# Ai_Breakout_OLED-0_96.net
KiCad netlist of a schematic drawn in EAGLE
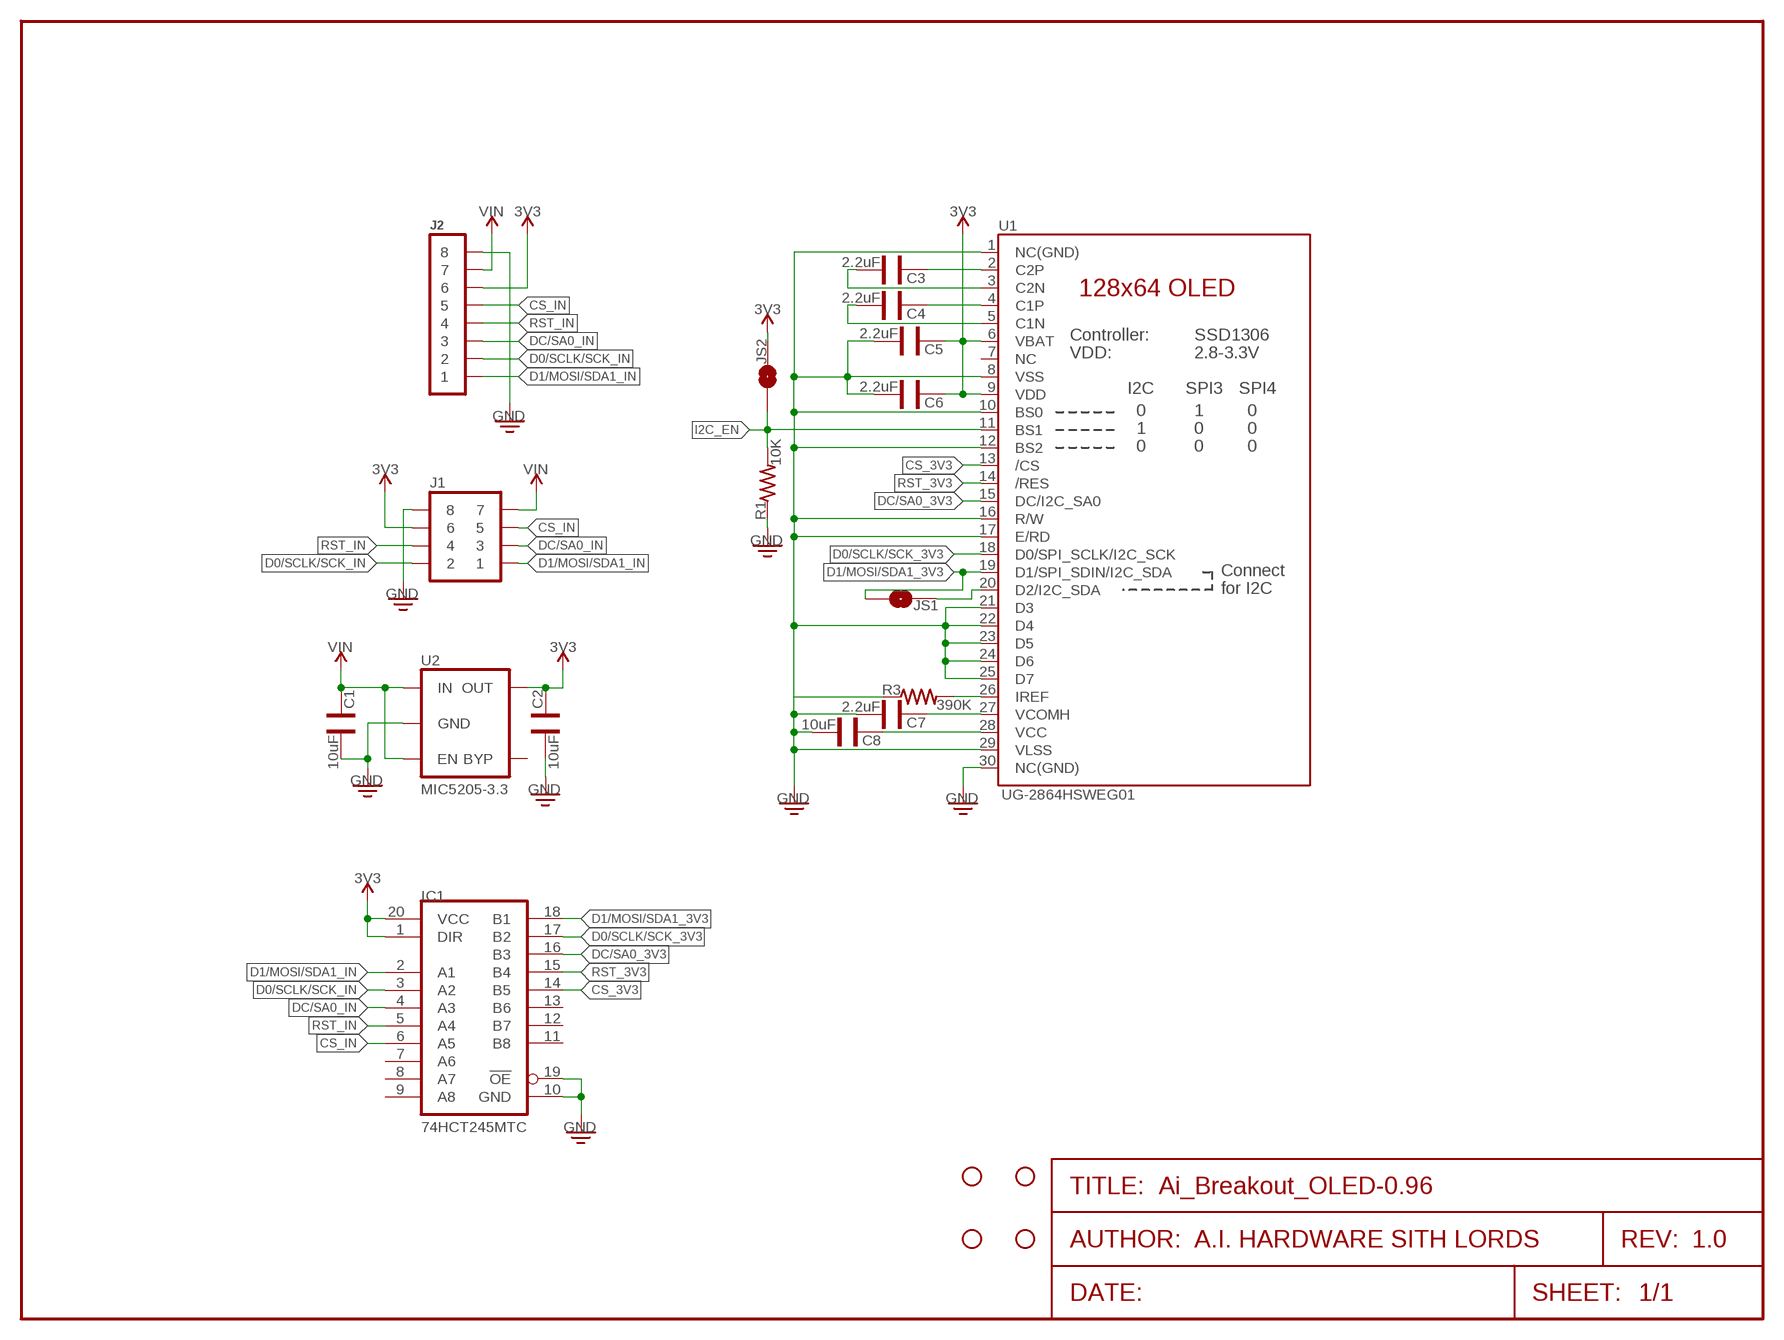
[diagram p0: schematic, sheet 1]

(export (version "E")
  (design (tool "Eeschema 10.0.6"))
  (components
    (comp (ref "C1")
      (value "10uF")
      (footprint "eagle-import:CAP-0603")
      (libsource (lib "eagle-import") (part "CAP0603"))
    )
    (comp (ref "C2")
      (value "10uF")
      (footprint "eagle-import:CAP-0603")
      (libsource (lib "eagle-import") (part "CAP0603"))
    )
    (comp (ref "C3")
      (value "2.2uF")
      (footprint "eagle-import:CAP-0603")
      (libsource (lib "eagle-import") (part "CAP0603"))
    )
    (comp (ref "C4")
      (value "2.2uF")
      (footprint "eagle-import:CAP-0603")
      (libsource (lib "eagle-import") (part "CAP0603"))
    )
    (comp (ref "C5")
      (value "2.2uF")
      (footprint "eagle-import:CAP-0603")
      (libsource (lib "eagle-import") (part "CAP0603"))
    )
    (comp (ref "C6")
      (value "2.2uF")
      (footprint "eagle-import:CAP-0603")
      (libsource (lib "eagle-import") (part "CAP0603"))
    )
    (comp (ref "C7")
      (value "2.2uF")
      (footprint "eagle-import:CAP-0603")
      (libsource (lib "eagle-import") (part "CAP0603"))
    )
    (comp (ref "C8")
      (value "10uF")
      (footprint "eagle-import:CAP-0603")
      (libsource (lib "eagle-import") (part "CAP0603"))
    )
    (comp (ref "IC1")
      (value "74HCT245MTC")
      (footprint "eagle-import:SSOP20")
      (libsource (lib "eagle-import") (part "74HCT245MTC"))
    )
    (comp (ref "J1")
      (value "2X04")
      (footprint "eagle-import:2X04")
      (libsource (lib "eagle-import") (part "2X04"))
    )
    (comp (ref "J2")
      (value "1X08")
      (footprint "eagle-import:1X08")
      (libsource (lib "eagle-import") (part "1X08"))
    )
    (comp (ref "JS1")
      (value "1X02-SJ-NO")
      (footprint "eagle-import:1X02-SJ-NO")
      (libsource (lib "eagle-import") (part "1X02-SJ-NO"))
    )
    (comp (ref "JS2")
      (value "1X02-SJ-NO")
      (footprint "eagle-import:1X02-SJ-NO")
      (libsource (lib "eagle-import") (part "1X02-SJ-NO"))
    )
    (comp (ref "M1")
      (value "STAND-OFF")
      (footprint "eagle-import:STAND-OFF")
      (libsource (lib "eagle-import") (part "STAND-OFF"))
    )
    (comp (ref "M2")
      (value "STAND-OFF")
      (footprint "eagle-import:STAND-OFF")
      (libsource (lib "eagle-import") (part "STAND-OFF"))
    )
    (comp (ref "M3")
      (value "STAND-OFF")
      (footprint "eagle-import:STAND-OFF")
      (libsource (lib "eagle-import") (part "STAND-OFF"))
    )
    (comp (ref "M4")
      (value "STAND-OFF")
      (footprint "eagle-import:STAND-OFF")
      (libsource (lib "eagle-import") (part "STAND-OFF"))
    )
    (comp (ref "R1")
      (value "10K")
      (footprint "eagle-import:RES-0603")
      (libsource (lib "eagle-import") (part "RES0603"))
    )
    (comp (ref "R3")
      (value "390K")
      (footprint "eagle-import:RES-0603")
      (libsource (lib "eagle-import") (part "RES0603"))
    )
    (comp (ref "U1")
      (value "UG-2864HSWEG01")
      (footprint "eagle-import:UG-2864HSWEG01_0.96_WRAP")
      (libsource (lib "eagle-import") (part "UG-2864HSWEG01-0.96"))
    )
    (comp (ref "U2")
      (value "MIC5205-3.3")
      (footprint "eagle-import:SOT23-5")
      (libsource (lib "eagle-import") (part "MIC5205-3.3"))
    )
  )
  (nets
    (net (code "1") (name "3V3") (class "Default")
      (node (ref "C2") (pin "2") (pinfunction "2_2") (pintype "passive"))
      (node (ref "C5") (pin "2") (pinfunction "2_2") (pintype "passive"))
      (node (ref "C6") (pin "2") (pinfunction "2_2") (pintype "passive"))
      (node (ref "IC1") (pin "1") (pinfunction "DIR_1") (pintype "input"))
      (node (ref "IC1") (pin "20") (pinfunction "VCC_20") (pintype "power_in"))
      (node (ref "J1") (pin "6") (pinfunction "6_6") (pintype "bidirectional"))
      (node (ref "J2") (pin "6") (pinfunction "6_6") (pintype "bidirectional"))
      (node (ref "JS2") (pin "2") (pinfunction "2_2") (pintype "passive"))
      (node (ref "U1") (pin "6") (pinfunction "VBAT_6") (pintype "input"))
      (node (ref "U1") (pin "9") (pinfunction "VDD_9") (pintype "power_in"))
      (node (ref "U2") (pin "5") (pinfunction "OUT_5") (pintype "passive"))
    )
    (net (code "2") (name "CS_3V3") (class "Default")
      (node (ref "IC1") (pin "14") (pinfunction "B5_14") (pintype "bidirectional"))
      (node (ref "U1") (pin "13") (pinfunction "/CS_13") (pintype "input"))
    )
    (net (code "3") (name "CS_IN") (class "Default")
      (node (ref "IC1") (pin "6") (pinfunction "A5_6") (pintype "bidirectional"))
      (node (ref "J1") (pin "5") (pinfunction "5_5") (pintype "bidirectional"))
      (node (ref "J2") (pin "5") (pinfunction "5_5") (pintype "bidirectional"))
    )
    (net (code "4") (name "D0{slash}SCLK{slash}SCK_3V3") (class "Default")
      (node (ref "IC1") (pin "17") (pinfunction "B2_17") (pintype "bidirectional"))
      (node (ref "U1") (pin "18") (pinfunction "D0/SPI_SCLK/I2C_SCK_18") (pintype "bidirectional"))
    )
    (net (code "5") (name "D0{slash}SCLK{slash}SCK_IN") (class "Default")
      (node (ref "IC1") (pin "3") (pinfunction "A2_3") (pintype "bidirectional"))
      (node (ref "J1") (pin "2") (pinfunction "2_2") (pintype "bidirectional"))
      (node (ref "J2") (pin "2") (pinfunction "2_2") (pintype "bidirectional"))
    )
    (net (code "6") (name "D1{slash}MOSI{slash}SDA1_3V3") (class "Default")
      (node (ref "IC1") (pin "18") (pinfunction "B1_18") (pintype "bidirectional"))
      (node (ref "JS1") (pin "1") (pinfunction "1_1") (pintype "passive"))
      (node (ref "U1") (pin "19") (pinfunction "D1/SPI_SDIN/I2C_SDA_19") (pintype "bidirectional"))
    )
    (net (code "7") (name "D1{slash}MOSI{slash}SDA1_IN") (class "Default")
      (node (ref "IC1") (pin "2") (pinfunction "A1_2") (pintype "bidirectional"))
      (node (ref "J1") (pin "1") (pinfunction "1_1") (pintype "bidirectional"))
      (node (ref "J2") (pin "1") (pinfunction "1_1") (pintype "bidirectional"))
    )
    (net (code "8") (name "DC{slash}SA0_3V3") (class "Default")
      (node (ref "IC1") (pin "16") (pinfunction "B3_16") (pintype "bidirectional"))
      (node (ref "U1") (pin "15") (pinfunction "DC/I2C_SA0_15") (pintype "input"))
    )
    (net (code "9") (name "DC{slash}SA0_IN") (class "Default")
      (node (ref "IC1") (pin "4") (pinfunction "A3_4") (pintype "bidirectional"))
      (node (ref "J1") (pin "3") (pinfunction "3_3") (pintype "bidirectional"))
      (node (ref "J2") (pin "3") (pinfunction "3_3") (pintype "bidirectional"))
    )
    (net (code "10") (name "GND") (class "Default")
      (node (ref "C1") (pin "1") (pinfunction "1_1") (pintype "passive"))
      (node (ref "C2") (pin "1") (pinfunction "1_1") (pintype "passive"))
      (node (ref "C5") (pin "1") (pinfunction "1_1") (pintype "passive"))
      (node (ref "C6") (pin "1") (pinfunction "1_1") (pintype "passive"))
      (node (ref "C7") (pin "1") (pinfunction "1_1") (pintype "passive"))
      (node (ref "C8") (pin "1") (pinfunction "1_1") (pintype "passive"))
      (node (ref "IC1") (pin "10") (pinfunction "GND_10") (pintype "power_in"))
      (node (ref "IC1") (pin "19") (pinfunction "~{OE}_19") (pintype "input"))
      (node (ref "J1") (pin "8") (pinfunction "8_8") (pintype "bidirectional"))
      (node (ref "J2") (pin "8") (pinfunction "8_8") (pintype "bidirectional"))
      (node (ref "R1") (pin "1") (pinfunction "1_1") (pintype "passive"))
      (node (ref "R3") (pin "1") (pinfunction "1_1") (pintype "passive"))
      (node (ref "U1") (pin "1") (pinfunction "NC(GND)_1") (pintype "input"))
      (node (ref "U1") (pin "10") (pinfunction "BS0_10") (pintype "input"))
      (node (ref "U1") (pin "12") (pinfunction "BS2_12") (pintype "input"))
      (node (ref "U1") (pin "16") (pinfunction "R/W_16") (pintype "input"))
      (node (ref "U1") (pin "17") (pinfunction "E/RD_17") (pintype "input"))
      (node (ref "U1") (pin "21") (pinfunction "D3_21") (pintype "bidirectional"))
      (node (ref "U1") (pin "22") (pinfunction "D4_22") (pintype "bidirectional"))
      (node (ref "U1") (pin "23") (pinfunction "D5_23") (pintype "bidirectional"))
      (node (ref "U1") (pin "24") (pinfunction "D6_24") (pintype "bidirectional"))
      (node (ref "U1") (pin "25") (pinfunction "D7_25") (pintype "bidirectional"))
      (node (ref "U1") (pin "29") (pinfunction "VLSS_29") (pintype "power_in"))
      (node (ref "U1") (pin "30") (pinfunction "NC(GND)_30") (pintype "input"))
      (node (ref "U1") (pin "8") (pinfunction "VSS_8") (pintype "power_in"))
      (node (ref "U2") (pin "2") (pinfunction "GND_2") (pintype "input"))
    )
    (net (code "11") (name "I2C_EN") (class "Default")
      (node (ref "JS2") (pin "1") (pinfunction "1_1") (pintype "passive"))
      (node (ref "R1") (pin "2") (pinfunction "2_2") (pintype "passive"))
      (node (ref "U1") (pin "11") (pinfunction "BS1_11") (pintype "input"))
    )
    (net (code "12") (name "Net-(U1-C1N)") (class "Default")
      (node (ref "C4") (pin "1") (pinfunction "1_1") (pintype "passive"))
      (node (ref "U1") (pin "5") (pinfunction "C1N_5") (pintype "input"))
    )
    (net (code "13") (name "Net-(U1-C1P)") (class "Default")
      (node (ref "C4") (pin "2") (pinfunction "2_2") (pintype "passive"))
      (node (ref "U1") (pin "4") (pinfunction "C1P_4") (pintype "input"))
    )
    (net (code "14") (name "Net-(U1-C2N)") (class "Default")
      (node (ref "C3") (pin "1") (pinfunction "1_1") (pintype "passive"))
      (node (ref "U1") (pin "3") (pinfunction "C2N_3") (pintype "input"))
    )
    (net (code "15") (name "Net-(U1-C2P)") (class "Default")
      (node (ref "C3") (pin "2") (pinfunction "2_2") (pintype "passive"))
      (node (ref "U1") (pin "2") (pinfunction "C2P_2") (pintype "input"))
    )
    (net (code "16") (name "Net-(U1-D2{slash}I2C_SDA)") (class "Default")
      (node (ref "JS1") (pin "2") (pinfunction "2_2") (pintype "passive"))
      (node (ref "U1") (pin "20") (pinfunction "D2/I2C_SDA_20") (pintype "bidirectional"))
    )
    (net (code "17") (name "Net-(U1-IREF)") (class "Default")
      (node (ref "R3") (pin "2") (pinfunction "2_2") (pintype "passive"))
      (node (ref "U1") (pin "26") (pinfunction "IREF_26") (pintype "input"))
    )
    (net (code "18") (name "Net-(U1-VCC)") (class "Default")
      (node (ref "C8") (pin "2") (pinfunction "2_2") (pintype "passive"))
      (node (ref "U1") (pin "28") (pinfunction "VCC_28") (pintype "power_in"))
    )
    (net (code "19") (name "Net-(U1-VCOMH)") (class "Default")
      (node (ref "C7") (pin "2") (pinfunction "2_2") (pintype "passive"))
      (node (ref "U1") (pin "27") (pinfunction "VCOMH_27") (pintype "output"))
    )
    (net (code "20") (name "RST_3V3") (class "Default")
      (node (ref "IC1") (pin "15") (pinfunction "B4_15") (pintype "bidirectional"))
      (node (ref "U1") (pin "14") (pinfunction "/RES_14") (pintype "input"))
    )
    (net (code "21") (name "RST_IN") (class "Default")
      (node (ref "IC1") (pin "5") (pinfunction "A4_5") (pintype "bidirectional"))
      (node (ref "J1") (pin "4") (pinfunction "4_4") (pintype "bidirectional"))
      (node (ref "J2") (pin "4") (pinfunction "4_4") (pintype "bidirectional"))
    )
    (net (code "22") (name "VIN") (class "Default")
      (node (ref "C1") (pin "2") (pinfunction "2_2") (pintype "passive"))
      (node (ref "J1") (pin "7") (pinfunction "7_7") (pintype "bidirectional"))
      (node (ref "J2") (pin "7") (pinfunction "7_7") (pintype "bidirectional"))
      (node (ref "U2") (pin "1") (pinfunction "IN_1") (pintype "input"))
      (node (ref "U2") (pin "3") (pinfunction "EN_3") (pintype "input"))
    )
    (net (code "23") (name "unconnected-(IC1-A6-Pad7)") (class "Default")
      (node (ref "IC1") (pin "7") (pinfunction "A6_7") (pintype "bidirectional"))
    )
    (net (code "24") (name "unconnected-(IC1-A7-Pad8)") (class "Default")
      (node (ref "IC1") (pin "8") (pinfunction "A7_8") (pintype "bidirectional"))
    )
    (net (code "25") (name "unconnected-(IC1-A8-Pad9)") (class "Default")
      (node (ref "IC1") (pin "9") (pinfunction "A8_9") (pintype "bidirectional"))
    )
    (net (code "26") (name "unconnected-(IC1-B6-Pad13)") (class "Default")
      (node (ref "IC1") (pin "13") (pinfunction "B6_13") (pintype "bidirectional"))
    )
    (net (code "27") (name "unconnected-(IC1-B7-Pad12)") (class "Default")
      (node (ref "IC1") (pin "12") (pinfunction "B7_12") (pintype "bidirectional"))
    )
    (net (code "28") (name "unconnected-(IC1-B8-Pad11)") (class "Default")
      (node (ref "IC1") (pin "11") (pinfunction "B8_11") (pintype "bidirectional"))
    )
    (net (code "29") (name "unconnected-(U1-NC-Pad7)") (class "Default")
      (node (ref "U1") (pin "7") (pinfunction "NC_7") (pintype "no_connect"))
    )
    (net (code "30") (name "unconnected-(U2-BYP-Pad4)") (class "Default")
      (node (ref "U2") (pin "4") (pinfunction "BYP_4") (pintype "input"))
    )
  )
)
